# output.net
KiCad netlist of a schematic drawn in Altium Designer
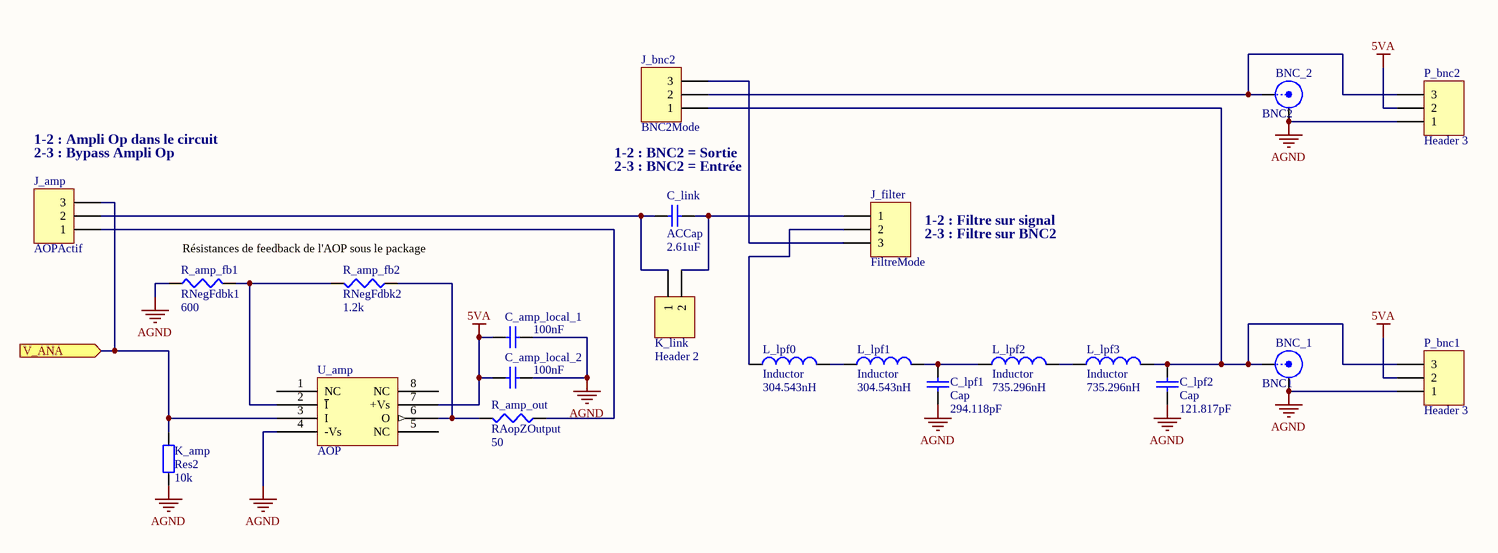
[diagram p0: output.SchDoc]

(export (version "E")
  (design (tool "Eeschema 10.0.6"))
  (components
    (comp (ref "BNC_1")
      (value "BNC1")
      (footprint "BNC_RA CON")
      (description "BNC Elbow Connector")
      (fields (field (name "PUBLISHER") "Altium Limited"))
      (libsource (lib "Miscellaneous Connectors") (part "BNC"))
    )
    (comp (ref "BNC_2")
      (value "BNC2")
      (footprint "BNC_RA CON")
      (description "BNC Elbow Connector")
      (fields (field (name "PUBLISHER") "Altium Limited"))
      (libsource (lib "Miscellaneous Connectors") (part "BNC"))
    )
    (comp (ref "C_amp_local_1")
      (value "100nF")
      (footprint "ourprints:0805")
      (description "Capacitor (Semiconductor SIM Model)")
      (fields (field (name "Comment") "Cap Semi") (field (name "PUBLISHER") "Altium Limited"))
      (libsource (lib "Miscellaneous Devices") (part "Cap Semi"))
    )
    (comp (ref "C_amp_local_2")
      (value "100nF")
      (footprint "ourprints:0805")
      (description "Capacitor (Semiconductor SIM Model)")
      (fields (field (name "Comment") "Cap Semi") (field (name "PUBLISHER") "Altium Limited"))
      (libsource (lib "Miscellaneous Devices") (part "Cap Semi"))
    )
    (comp (ref "C_link")
      (value "ACCap")
      (footprint "ourprints:0805")
      (description "Capacitor")
      (fields (field (name "ALTIUM_VALUE") "2.61uF") (field (name "PUBLISHER") "Altium Limited"))
      (libsource (lib "Miscellaneous Devices") (part "Cap"))
    )
    (comp (ref "C_lpf1")
      (value "Cap")
      (footprint "ourprints:0805")
      (description "Capacitor")
      (fields (field (name "ALTIUM_VALUE") "294.118pF") (field (name "PUBLISHER") "Altium Limited"))
      (libsource (lib "Miscellaneous Devices") (part "Cap"))
    )
    (comp (ref "C_lpf2")
      (value "Cap")
      (footprint "ourprints:0805")
      (description "Capacitor")
      (fields (field (name "ALTIUM_VALUE") "121.817pF") (field (name "PUBLISHER") "Altium Limited"))
      (libsource (lib "Miscellaneous Devices") (part "Cap"))
    )
    (comp (ref "J_amp")
      (value "AOPActif")
      (footprint "HDR1X3")
      (description "Header, 3-Pin")
      (fields (field (name "PUBLISHER") "Altium Limited"))
      (libsource (lib "Miscellaneous Connectors") (part "Header 3"))
    )
    (comp (ref "J_bnc2")
      (value "BNC2Mode")
      (footprint "HDR1X3")
      (description "Header, 3-Pin")
      (fields (field (name "PUBLISHER") "Altium Limited"))
      (libsource (lib "Miscellaneous Connectors") (part "Header 3"))
    )
    (comp (ref "J_filter")
      (value "FiltreMode")
      (footprint "HDR1X3")
      (description "Header, 3-Pin")
      (fields (field (name "PUBLISHER") "Altium Limited"))
      (libsource (lib "") (part "Header 3_2"))
    )
    (comp (ref "K_amp")
      (value "Res2")
      (footprint "ourprints:0805")
      (description "Resistor")
      (fields (field (name "ALTIUM_VALUE") "10k") (field (name "PUBLISHER") "Altium Limited"))
      (libsource (lib "Miscellaneous Devices") (part "Res2"))
    )
    (comp (ref "K_link")
      (value "Header 2")
      (footprint "HDR1X2")
      (description "Header, 2-Pin")
      (fields (field (name "PUBLISHER") "Altium Limited"))
      (libsource (lib "Miscellaneous Connectors") (part "Header 2"))
    )
    (comp (ref "L_lpf0")
      (value "Inductor")
      (footprint "ourprints:0805")
      (fields (field (name "ALTIUM_VALUE") "304.543nH") (field (name "PUBLISHER") "Altium Limited"))
      (libsource (lib "Miscellaneous Devices") (part "Inductor"))
    )
    (comp (ref "L_lpf1")
      (value "Inductor")
      (footprint "ourprints:0805")
      (fields (field (name "ALTIUM_VALUE") "304.543nH") (field (name "PUBLISHER") "Altium Limited"))
      (libsource (lib "Miscellaneous Devices") (part "Inductor"))
    )
    (comp (ref "L_lpf2")
      (value "Inductor")
      (footprint "ourprints:0805")
      (fields (field (name "ALTIUM_VALUE") "735.296nH") (field (name "PUBLISHER") "Altium Limited"))
      (libsource (lib "Miscellaneous Devices") (part "Inductor"))
    )
    (comp (ref "L_lpf3")
      (value "Inductor")
      (footprint "ourprints:0805")
      (fields (field (name "ALTIUM_VALUE") "735.296nH") (field (name "PUBLISHER") "Altium Limited"))
      (libsource (lib "Miscellaneous Devices") (part "Inductor"))
    )
    (comp (ref "P_bnc1")
      (value "Header 3")
      (footprint "HDR1X3")
      (description "Header, 3-Pin")
      (fields (field (name "PUBLISHER") "Altium Limited"))
      (libsource (lib "") (part "Header 3_1"))
    )
    (comp (ref "P_bnc2")
      (value "Header 3")
      (footprint "HDR1X3")
      (description "Header, 3-Pin")
      (fields (field (name "PUBLISHER") "Altium Limited"))
      (libsource (lib "") (part "Header 3_1"))
    )
    (comp (ref "R_amp_fb1")
      (value "RNegFdbk1")
      (footprint "ourprints:0805")
      (description "Resistor")
      (fields (field (name "ALTIUM_VALUE") "600") (field (name "PUBLISHER") "Altium Limited"))
      (libsource (lib "Miscellaneous Devices") (part "Res3"))
    )
    (comp (ref "R_amp_fb2")
      (value "RNegFdbk2")
      (footprint "ourprints:0805")
      (description "Resistor")
      (fields (field (name "ALTIUM_VALUE") "1.2k") (field (name "PUBLISHER") "Altium Limited"))
      (libsource (lib "Miscellaneous Devices") (part "Res3"))
    )
    (comp (ref "R_amp_out")
      (value "RAopZOutput")
      (footprint "ourprints:0805")
      (description "Resistor")
      (fields (field (name "ALTIUM_VALUE") "50") (field (name "PUBLISHER") "Altium Limited"))
      (libsource (lib "Miscellaneous Devices") (part "Res3"))
    )
    (comp (ref "U_amp") (value "AOP") (footprint "SOIC127P600-8CN") (libsource (lib "ourlibs") (part "AOP")))
  )
  (nets
    (net (code "1") (name "/V_ANA") (class "Default")
      (node (ref "J_amp") (pin "3") (pinfunction "3_3") (pintype "passive"))
      (node (ref "K_amp") (pin "2") (pinfunction "2_2") (pintype "passive"))
      (node (ref "U_amp") (pin "3") (pinfunction "I_3") (pintype "passive"))
    )
    (net (code "2") (name "5VA") (class "Default")
      (node (ref "C_amp_local_1") (pin "2") (pinfunction "2_2") (pintype "passive"))
      (node (ref "C_amp_local_2") (pin "2") (pinfunction "2_2") (pintype "passive"))
      (node (ref "P_bnc1") (pin "2") (pinfunction "2_2") (pintype "passive"))
      (node (ref "P_bnc2") (pin "2") (pinfunction "2_2") (pintype "passive"))
      (node (ref "U_amp") (pin "7") (pinfunction "+Vs_7") (pintype "power_in"))
    )
    (net (code "3") (name "AGND") (class "Default")
      (node (ref "BNC_1") (pin "2") (pinfunction "Y_2") (pintype "passive"))
      (node (ref "BNC_2") (pin "2") (pinfunction "Y_2") (pintype "passive"))
      (node (ref "C_amp_local_1") (pin "1") (pinfunction "1_1") (pintype "passive"))
      (node (ref "C_amp_local_2") (pin "1") (pinfunction "1_1") (pintype "passive"))
      (node (ref "C_lpf1") (pin "1") (pinfunction "1_1") (pintype "passive"))
      (node (ref "C_lpf2") (pin "1") (pinfunction "1_1") (pintype "passive"))
      (node (ref "K_amp") (pin "1") (pinfunction "1_1") (pintype "passive"))
      (node (ref "P_bnc1") (pin "1") (pinfunction "1_1") (pintype "passive"))
      (node (ref "P_bnc2") (pin "1") (pinfunction "1_1") (pintype "passive"))
      (node (ref "R_amp_fb1") (pin "1") (pinfunction "1_1") (pintype "passive"))
      (node (ref "U_amp") (pin "4") (pinfunction "-Vs_4") (pintype "power_in"))
    )
    (net (code "4") (name "Net-(BNC_1-X)") (class "Default")
      (node (ref "BNC_1") (pin "1") (pinfunction "X_1") (pintype "passive"))
      (node (ref "C_lpf2") (pin "2") (pinfunction "2_2") (pintype "passive"))
      (node (ref "J_bnc2") (pin "1") (pinfunction "1_1") (pintype "passive"))
      (node (ref "L_lpf3") (pin "2") (pinfunction "2_2") (pintype "passive"))
      (node (ref "P_bnc1") (pin "3") (pinfunction "3_3") (pintype "passive"))
    )
    (net (code "5") (name "Net-(BNC_2-X)") (class "Default")
      (node (ref "BNC_2") (pin "1") (pinfunction "X_1") (pintype "passive"))
      (node (ref "J_bnc2") (pin "2") (pinfunction "2_2") (pintype "passive"))
      (node (ref "P_bnc2") (pin "3") (pinfunction "3_3") (pintype "passive"))
    )
    (net (code "6") (name "Net-(C_link-Pad1)") (class "Default")
      (node (ref "C_link") (pin "1") (pinfunction "1_1") (pintype "passive"))
      (node (ref "J_amp") (pin "2") (pinfunction "2_2") (pintype "passive"))
      (node (ref "K_link") (pin "1") (pinfunction "1_1") (pintype "passive"))
    )
    (net (code "7") (name "Net-(C_link-Pad2)") (class "Default")
      (node (ref "C_link") (pin "2") (pinfunction "2_2") (pintype "passive"))
      (node (ref "J_filter") (pin "1") (pinfunction "1_1") (pintype "passive"))
      (node (ref "K_link") (pin "2") (pinfunction "2_2") (pintype "passive"))
    )
    (net (code "8") (name "Net-(C_lpf1-Pad2)") (class "Default")
      (node (ref "C_lpf1") (pin "2") (pinfunction "2_2") (pintype "passive"))
      (node (ref "L_lpf1") (pin "2") (pinfunction "2_2") (pintype "passive"))
      (node (ref "L_lpf2") (pin "1") (pinfunction "1_1") (pintype "passive"))
    )
    (net (code "9") (name "Net-(J_amp-Pad1)") (class "Default")
      (node (ref "J_amp") (pin "1") (pinfunction "1_1") (pintype "passive"))
      (node (ref "R_amp_out") (pin "1") (pinfunction "1_1") (pintype "passive"))
    )
    (net (code "10") (name "Net-(J_bnc2-Pad3)") (class "Default")
      (node (ref "J_bnc2") (pin "3") (pinfunction "3_3") (pintype "passive"))
      (node (ref "J_filter") (pin "3") (pinfunction "3_3") (pintype "passive"))
    )
    (net (code "11") (name "Net-(J_filter-Pad2)") (class "Default")
      (node (ref "J_filter") (pin "2") (pinfunction "2_2") (pintype "passive"))
      (node (ref "L_lpf0") (pin "1") (pinfunction "1_1") (pintype "passive"))
    )
    (net (code "12") (name "Net-(L_lpf0-Pad2)") (class "Default")
      (node (ref "L_lpf0") (pin "2") (pinfunction "2_2") (pintype "passive"))
      (node (ref "L_lpf1") (pin "1") (pinfunction "1_1") (pintype "passive"))
    )
    (net (code "13") (name "Net-(L_lpf2-Pad2)") (class "Default")
      (node (ref "L_lpf2") (pin "2") (pinfunction "2_2") (pintype "passive"))
      (node (ref "L_lpf3") (pin "1") (pinfunction "1_1") (pintype "passive"))
    )
    (net (code "14") (name "Net-(U_amp-O)") (class "Default")
      (node (ref "R_amp_fb2") (pin "1") (pinfunction "1_1") (pintype "passive"))
      (node (ref "R_amp_out") (pin "2") (pinfunction "2_2") (pintype "passive"))
      (node (ref "U_amp") (pin "6") (pinfunction "O_6") (pintype "output"))
    )
    (net (code "15") (name "Net-(U_amp-~{I})") (class "Default")
      (node (ref "R_amp_fb1") (pin "2") (pinfunction "2_2") (pintype "passive"))
      (node (ref "R_amp_fb2") (pin "2") (pinfunction "2_2") (pintype "passive"))
      (node (ref "U_amp") (pin "2") (pinfunction "~{I}_2") (pintype "passive"))
    )
    (net (code "16") (name "unconnected-(U_amp-NC-Pad1)") (class "Default")
      (node (ref "U_amp") (pin "1") (pinfunction "NC_1") (pintype "passive"))
    )
    (net (code "17") (name "unconnected-(U_amp-NC-Pad5)") (class "Default")
      (node (ref "U_amp") (pin "5") (pinfunction "NC_5") (pintype "passive"))
    )
    (net (code "18") (name "unconnected-(U_amp-NC-Pad8)") (class "Default")
      (node (ref "U_amp") (pin "8") (pinfunction "NC_8") (pintype "passive"))
    )
  )
)
